# extboard.net
KiCad netlist of a schematic drawn in EAGLE
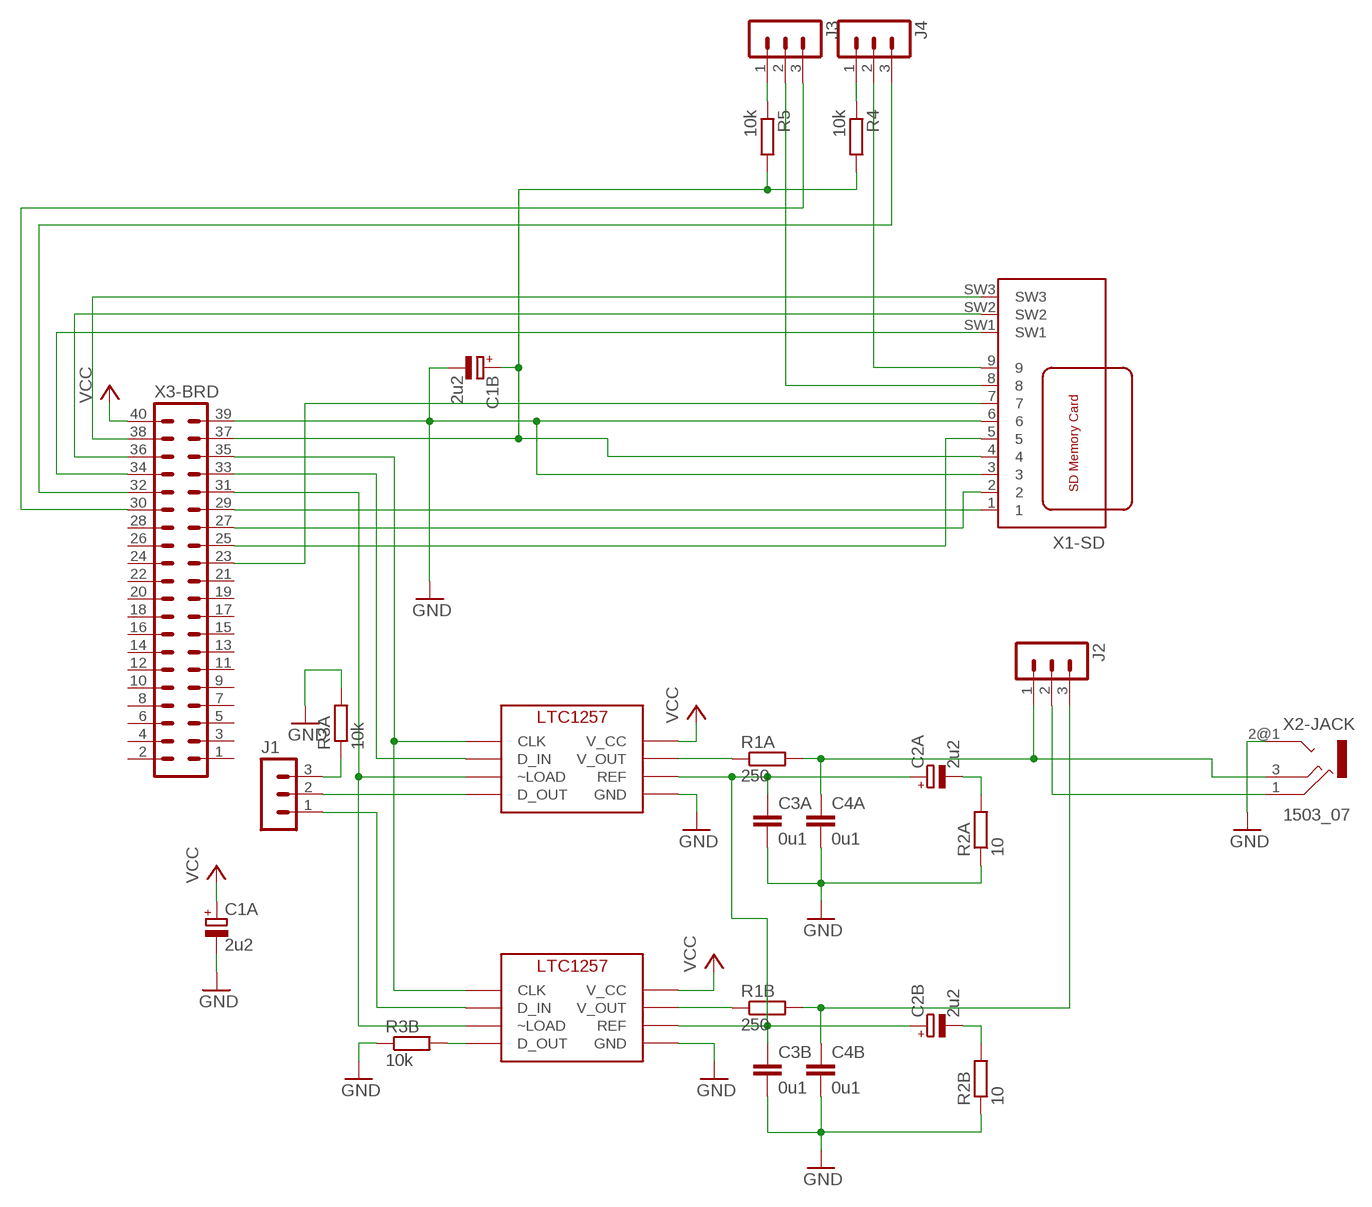
[diagram p0: schematic, sheet 1]

(export (version "E")
  (design (tool "Eeschema 10.0.6"))
  (components
    (comp (ref "C1A")
      (value "2u2")
      (footprint "eagle-import:E2,5-7")
      (libsource (lib "eagle-import") (part "CPOL-EUE2.5-7"))
    )
    (comp (ref "C1B")
      (value "2u2")
      (footprint "eagle-import:E2,5-7")
      (libsource (lib "eagle-import") (part "CPOL-EUE2.5-7"))
    )
    (comp (ref "C2A")
      (value "2u2")
      (footprint "eagle-import:E2,5-7")
      (libsource (lib "eagle-import") (part "CPOL-EUE2.5-7"))
    )
    (comp (ref "C2B")
      (value "2u2")
      (footprint "eagle-import:E2,5-7")
      (libsource (lib "eagle-import") (part "CPOL-EUE2.5-7"))
    )
    (comp (ref "C3A")
      (value "0u1")
      (footprint "eagle-import:C050-025X075")
      (libsource (lib "eagle-import") (part "C-EU050-025X075"))
    )
    (comp (ref "C3B")
      (value "0u1")
      (footprint "eagle-import:C050-025X075")
      (libsource (lib "eagle-import") (part "C-EU050-025X075"))
    )
    (comp (ref "C4A")
      (value "0u1")
      (footprint "eagle-import:C050-025X075")
      (libsource (lib "eagle-import") (part "C-EU050-025X075"))
    )
    (comp (ref "C4B")
      (value "0u1")
      (footprint "eagle-import:C050-025X075")
      (libsource (lib "eagle-import") (part "C-EU050-025X075"))
    )
    (comp (ref "J1")
      (value "MA03-1")
      (footprint "eagle-import:MA03-1")
      (libsource (lib "eagle-import") (part "MA03-1"))
    )
    (comp (ref "J2")
      (value "MA03-1")
      (footprint "eagle-import:MA03-1")
      (libsource (lib "eagle-import") (part "MA03-1"))
    )
    (comp (ref "J3")
      (value "MA03-1")
      (footprint "eagle-import:MA03-1")
      (fields (field (name "OC_FARNELL") "unknown") (field (name "OC_NEWARK") "unknown"))
      (libsource (lib "eagle-import") (part "MA03-1"))
    )
    (comp (ref "J4")
      (value "MA03-1")
      (footprint "eagle-import:MA03-1")
      (fields (field (name "OC_FARNELL") "unknown") (field (name "OC_NEWARK") "unknown"))
      (libsource (lib "eagle-import") (part "MA03-1"))
    )
    (comp (ref "R1A")
      (value "250")
      (footprint "eagle-import:0207_10")
      (libsource (lib "eagle-import") (part "R-EU_0207/10"))
    )
    (comp (ref "R1B")
      (value "250")
      (footprint "eagle-import:0207_10")
      (libsource (lib "eagle-import") (part "R-EU_0207/10"))
    )
    (comp (ref "R2A")
      (value "10")
      (footprint "eagle-import:0207_10")
      (libsource (lib "eagle-import") (part "R-EU_0207/10"))
    )
    (comp (ref "R2B")
      (value "10")
      (footprint "eagle-import:0207_10")
      (libsource (lib "eagle-import") (part "R-EU_0207/10"))
    )
    (comp (ref "R3A")
      (value "10k")
      (footprint "eagle-import:0207_10")
      (libsource (lib "eagle-import") (part "R-EU_0207/10"))
    )
    (comp (ref "R3B")
      (value "10k")
      (footprint "eagle-import:0207_10")
      (libsource (lib "eagle-import") (part "R-EU_0207/10"))
    )
    (comp (ref "R4")
      (value "10k")
      (footprint "eagle-import:0207_10")
      (libsource (lib "eagle-import") (part "R-EU_0207/10"))
    )
    (comp (ref "R5")
      (value "10k")
      (footprint "eagle-import:0207_10")
      (libsource (lib "eagle-import") (part "R-EU_0207/10"))
    )
    (comp (ref "U1")
      (value "LTC1257")
      (footprint "eagle-import:DIL-8")
      (libsource (lib "eagle-import") (part "LTC1257"))
    )
    (comp (ref "U2")
      (value "LTC1257")
      (footprint "eagle-import:DIL-8")
      (libsource (lib "eagle-import") (part "LTC1257"))
    )
    (comp (ref "X1-SD")
      (value "SDBMF")
      (footprint "eagle-import:SDBMF-009XXBXX2")
      (libsource (lib "eagle-import") (part "SDBMF"))
    )
    (comp (ref "X2-JACK")
      (value "1503_07")
      (footprint "eagle-import:1503_07")
      (fields (field (name "OC_FARNELL") "unknown"))
      (libsource (lib "eagle-import") (part "1503_?07"))
    )
    (comp (ref "X3-BRD")
      (value "MA20-2W")
      (footprint "eagle-import:MA20-2W")
      (libsource (lib "eagle-import") (part "MA20-2W"))
    )
  )
  (nets
    (net (code "1") (name "GND") (class "Default")
      (node (ref "C1A") (pin "-") (pinfunction "-_-") (pintype "passive"))
      (node (ref "C1B") (pin "-") (pinfunction "-_-") (pintype "passive"))
      (node (ref "C3A") (pin "2") (pinfunction "2_2") (pintype "passive"))
      (node (ref "C3B") (pin "2") (pinfunction "2_2") (pintype "passive"))
      (node (ref "C4A") (pin "2") (pinfunction "2_2") (pintype "passive"))
      (node (ref "C4B") (pin "2") (pinfunction "2_2") (pintype "passive"))
      (node (ref "R2A") (pin "1") (pinfunction "1_1") (pintype "passive"))
      (node (ref "R2B") (pin "1") (pinfunction "1_1") (pintype "passive"))
      (node (ref "R3A") (pin "2") (pinfunction "2_2") (pintype "passive"))
      (node (ref "R3B") (pin "1") (pinfunction "1_1") (pintype "passive"))
      (node (ref "U1") (pin "P$5") (pinfunction "GND_P$5") (pintype "power_in"))
      (node (ref "U2") (pin "P$5") (pinfunction "GND_P$5") (pintype "power_in"))
      (node (ref "X1-SD") (pin "3") (pinfunction "3_3") (pintype "passive"))
      (node (ref "X1-SD") (pin "6") (pinfunction "6_6") (pintype "passive"))
      (node (ref "X2-JACK") (pin "2@1") (pinfunction "2_2@1") (pintype "passive"))
      (node (ref "X3-BRD") (pin "39") (pinfunction "39_39") (pintype "passive"))
    )
    (net (code "2") (name "Net-(C1B-Pad+)") (class "Default")
      (node (ref "C1B") (pin "+") (pinfunction "+_+") (pintype "passive"))
      (node (ref "R4") (pin "2") (pinfunction "2_2") (pintype "passive"))
      (node (ref "R5") (pin "2") (pinfunction "2_2") (pintype "passive"))
      (node (ref "X1-SD") (pin "4") (pinfunction "4_4") (pintype "passive"))
      (node (ref "X3-BRD") (pin "37") (pinfunction "37_37") (pintype "passive"))
    )
    (net (code "3") (name "Net-(C2A-Pad-)") (class "Default")
      (node (ref "C2A") (pin "-") (pinfunction "-_-") (pintype "passive"))
      (node (ref "R2A") (pin "2") (pinfunction "2_2") (pintype "passive"))
    )
    (net (code "4") (name "Net-(C2B-Pad-)") (class "Default")
      (node (ref "C2B") (pin "-") (pinfunction "-_-") (pintype "passive"))
      (node (ref "R2B") (pin "2") (pinfunction "2_2") (pintype "passive"))
    )
    (net (code "5") (name "Net-(C4A-Pad1)") (class "Default")
      (node (ref "C4A") (pin "1") (pinfunction "1_1") (pintype "passive"))
      (node (ref "J2") (pin "1") (pinfunction "1_1") (pintype "passive"))
      (node (ref "R1A") (pin "2") (pinfunction "2_2") (pintype "passive"))
      (node (ref "X2-JACK") (pin "3") (pinfunction "3_3") (pintype "passive"))
    )
    (net (code "6") (name "Net-(C4B-Pad1)") (class "Default")
      (node (ref "C4B") (pin "1") (pinfunction "1_1") (pintype "passive"))
      (node (ref "J2") (pin "3") (pinfunction "3_3") (pintype "passive"))
      (node (ref "R1B") (pin "2") (pinfunction "2_2") (pintype "passive"))
    )
    (net (code "7") (name "Net-(J1-Pad3)") (class "Default")
      (node (ref "J1") (pin "3") (pinfunction "3_3") (pintype "passive"))
      (node (ref "R3A") (pin "1") (pinfunction "1_1") (pintype "passive"))
    )
    (net (code "8") (name "Net-(J2-Pad2)") (class "Default")
      (node (ref "J2") (pin "2") (pinfunction "2_2") (pintype "passive"))
      (node (ref "X2-JACK") (pin "1") (pinfunction "1_1") (pintype "passive"))
    )
    (net (code "9") (name "Net-(J3-Pad1)") (class "Default")
      (node (ref "J3") (pin "1") (pinfunction "1_1") (pintype "passive"))
      (node (ref "R5") (pin "1") (pinfunction "1_1") (pintype "passive"))
    )
    (net (code "10") (name "Net-(J3-Pad2)") (class "Default")
      (node (ref "J3") (pin "2") (pinfunction "2_2") (pintype "passive"))
      (node (ref "X1-SD") (pin "8") (pinfunction "8_8") (pintype "passive"))
    )
    (net (code "11") (name "Net-(J3-Pad3)") (class "Default")
      (node (ref "J3") (pin "3") (pinfunction "3_3") (pintype "passive"))
      (node (ref "X3-BRD") (pin "30") (pinfunction "30_30") (pintype "passive"))
    )
    (net (code "12") (name "Net-(J4-Pad1)") (class "Default")
      (node (ref "J4") (pin "1") (pinfunction "1_1") (pintype "passive"))
      (node (ref "R4") (pin "1") (pinfunction "1_1") (pintype "passive"))
    )
    (net (code "13") (name "Net-(J4-Pad2)") (class "Default")
      (node (ref "J4") (pin "2") (pinfunction "2_2") (pintype "passive"))
      (node (ref "X1-SD") (pin "9") (pinfunction "9_9") (pintype "passive"))
    )
    (net (code "14") (name "Net-(J4-Pad3)") (class "Default")
      (node (ref "J4") (pin "3") (pinfunction "3_3") (pintype "passive"))
      (node (ref "X3-BRD") (pin "32") (pinfunction "32_32") (pintype "passive"))
    )
    (net (code "15") (name "Net-(U1-CLK)") (class "Default")
      (node (ref "U1") (pin "P$1") (pinfunction "CLK_P$1") (pintype "input"))
      (node (ref "U2") (pin "P$1") (pinfunction "CLK_P$1") (pintype "input"))
      (node (ref "X3-BRD") (pin "35") (pinfunction "35_35") (pintype "passive"))
    )
    (net (code "16") (name "Net-(U1-D_IN)") (class "Default")
      (node (ref "U1") (pin "P$2") (pinfunction "D_IN_P$2") (pintype "input"))
      (node (ref "X3-BRD") (pin "33") (pinfunction "33_33") (pintype "passive"))
    )
    (net (code "17") (name "Net-(U1-D_OUT)") (class "Default")
      (node (ref "J1") (pin "2") (pinfunction "2_2") (pintype "passive"))
      (node (ref "U1") (pin "P$4") (pinfunction "D_OUT_P$4") (pintype "output"))
    )
    (net (code "18") (name "Net-(U1-REF)") (class "Default")
      (node (ref "C2A") (pin "+") (pinfunction "+_+") (pintype "passive"))
      (node (ref "C2B") (pin "+") (pinfunction "+_+") (pintype "passive"))
      (node (ref "C3A") (pin "1") (pinfunction "1_1") (pintype "passive"))
      (node (ref "C3B") (pin "1") (pinfunction "1_1") (pintype "passive"))
      (node (ref "U1") (pin "P$6") (pinfunction "REF_P$6") (pintype "power_in"))
      (node (ref "U2") (pin "P$6") (pinfunction "REF_P$6") (pintype "power_in"))
    )
    (net (code "19") (name "Net-(U1-V_OUT)") (class "Default")
      (node (ref "R1A") (pin "1") (pinfunction "1_1") (pintype "passive"))
      (node (ref "U1") (pin "P$7") (pinfunction "V_OUT_P$7") (pintype "output"))
    )
    (net (code "20") (name "Net-(U1-~{LOAD})") (class "Default")
      (node (ref "U1") (pin "P$3") (pinfunction "~{LOAD}_P$3") (pintype "input"))
      (node (ref "U2") (pin "P$3") (pinfunction "~{LOAD}_P$3") (pintype "input"))
      (node (ref "X3-BRD") (pin "31") (pinfunction "31_31") (pintype "passive"))
    )
    (net (code "21") (name "Net-(U2-D_IN)") (class "Default")
      (node (ref "J1") (pin "1") (pinfunction "1_1") (pintype "passive"))
      (node (ref "U2") (pin "P$2") (pinfunction "D_IN_P$2") (pintype "input"))
    )
    (net (code "22") (name "Net-(U2-D_OUT)") (class "Default")
      (node (ref "R3B") (pin "2") (pinfunction "2_2") (pintype "passive"))
      (node (ref "U2") (pin "P$4") (pinfunction "D_OUT_P$4") (pintype "output"))
    )
    (net (code "23") (name "Net-(U2-V_OUT)") (class "Default")
      (node (ref "R1B") (pin "1") (pinfunction "1_1") (pintype "passive"))
      (node (ref "U2") (pin "P$7") (pinfunction "V_OUT_P$7") (pintype "output"))
    )
    (net (code "24") (name "Net-(X1-SD-Pad1)") (class "Default")
      (node (ref "X1-SD") (pin "1") (pinfunction "1_1") (pintype "passive"))
      (node (ref "X3-BRD") (pin "29") (pinfunction "29_29") (pintype "passive"))
    )
    (net (code "25") (name "Net-(X1-SD-Pad2)") (class "Default")
      (node (ref "X1-SD") (pin "2") (pinfunction "2_2") (pintype "passive"))
      (node (ref "X3-BRD") (pin "27") (pinfunction "27_27") (pintype "passive"))
    )
    (net (code "26") (name "Net-(X1-SD-Pad5)") (class "Default")
      (node (ref "X1-SD") (pin "5") (pinfunction "5_5") (pintype "passive"))
      (node (ref "X3-BRD") (pin "25") (pinfunction "25_25") (pintype "passive"))
    )
    (net (code "27") (name "Net-(X1-SD-Pad7)") (class "Default")
      (node (ref "X1-SD") (pin "7") (pinfunction "7_7") (pintype "passive"))
      (node (ref "X3-BRD") (pin "23") (pinfunction "23_23") (pintype "passive"))
    )
    (net (code "28") (name "Net-(X1-SD-PadSW1)") (class "Default")
      (node (ref "X1-SD") (pin "SW1") (pinfunction "SW1_SW1") (pintype "passive"))
      (node (ref "X3-BRD") (pin "34") (pinfunction "34_34") (pintype "passive"))
    )
    (net (code "29") (name "Net-(X1-SD-PadSW2)") (class "Default")
      (node (ref "X1-SD") (pin "SW2") (pinfunction "SW2_SW2") (pintype "passive"))
      (node (ref "X3-BRD") (pin "36") (pinfunction "36_36") (pintype "passive"))
    )
    (net (code "30") (name "Net-(X1-SD-PadSW3)") (class "Default")
      (node (ref "X1-SD") (pin "SW3") (pinfunction "SW3_SW3") (pintype "passive"))
      (node (ref "X3-BRD") (pin "38") (pinfunction "38_38") (pintype "passive"))
    )
    (net (code "31") (name "VCC") (class "Default")
      (node (ref "C1A") (pin "+") (pinfunction "+_+") (pintype "passive"))
      (node (ref "U1") (pin "P$8") (pinfunction "V_CC_P$8") (pintype "power_in"))
      (node (ref "U2") (pin "P$8") (pinfunction "V_CC_P$8") (pintype "power_in"))
      (node (ref "X3-BRD") (pin "40") (pinfunction "40_40") (pintype "passive"))
    )
    (net (code "32") (name "unconnected-(X2-JACK-2-Pad2@2)") (class "Default")
      (node (ref "X2-JACK") (pin "2@2") (pinfunction "2_2@2") (pintype "passive"))
    )
    (net (code "33") (name "unconnected-(X3-BRD-Pad1)") (class "Default")
      (node (ref "X3-BRD") (pin "1") (pinfunction "1_1") (pintype "passive"))
    )
    (net (code "34") (name "unconnected-(X3-BRD-Pad2)") (class "Default")
      (node (ref "X3-BRD") (pin "2") (pinfunction "2_2") (pintype "passive"))
    )
    (net (code "35") (name "unconnected-(X3-BRD-Pad3)") (class "Default")
      (node (ref "X3-BRD") (pin "3") (pinfunction "3_3") (pintype "passive"))
    )
    (net (code "36") (name "unconnected-(X3-BRD-Pad4)") (class "Default")
      (node (ref "X3-BRD") (pin "4") (pinfunction "4_4") (pintype "passive"))
    )
    (net (code "37") (name "unconnected-(X3-BRD-Pad5)") (class "Default")
      (node (ref "X3-BRD") (pin "5") (pinfunction "5_5") (pintype "passive"))
    )
    (net (code "38") (name "unconnected-(X3-BRD-Pad6)") (class "Default")
      (node (ref "X3-BRD") (pin "6") (pinfunction "6_6") (pintype "passive"))
    )
    (net (code "39") (name "unconnected-(X3-BRD-Pad7)") (class "Default")
      (node (ref "X3-BRD") (pin "7") (pinfunction "7_7") (pintype "passive"))
    )
    (net (code "40") (name "unconnected-(X3-BRD-Pad8)") (class "Default")
      (node (ref "X3-BRD") (pin "8") (pinfunction "8_8") (pintype "passive"))
    )
    (net (code "41") (name "unconnected-(X3-BRD-Pad9)") (class "Default")
      (node (ref "X3-BRD") (pin "9") (pinfunction "9_9") (pintype "passive"))
    )
    (net (code "42") (name "unconnected-(X3-BRD-Pad10)") (class "Default")
      (node (ref "X3-BRD") (pin "10") (pinfunction "10_10") (pintype "passive"))
    )
    (net (code "43") (name "unconnected-(X3-BRD-Pad11)") (class "Default")
      (node (ref "X3-BRD") (pin "11") (pinfunction "11_11") (pintype "passive"))
    )
    (net (code "44") (name "unconnected-(X3-BRD-Pad12)") (class "Default")
      (node (ref "X3-BRD") (pin "12") (pinfunction "12_12") (pintype "passive"))
    )
    (net (code "45") (name "unconnected-(X3-BRD-Pad13)") (class "Default")
      (node (ref "X3-BRD") (pin "13") (pinfunction "13_13") (pintype "passive"))
    )
    (net (code "46") (name "unconnected-(X3-BRD-Pad14)") (class "Default")
      (node (ref "X3-BRD") (pin "14") (pinfunction "14_14") (pintype "passive"))
    )
    (net (code "47") (name "unconnected-(X3-BRD-Pad15)") (class "Default")
      (node (ref "X3-BRD") (pin "15") (pinfunction "15_15") (pintype "passive"))
    )
    (net (code "48") (name "unconnected-(X3-BRD-Pad16)") (class "Default")
      (node (ref "X3-BRD") (pin "16") (pinfunction "16_16") (pintype "passive"))
    )
    (net (code "49") (name "unconnected-(X3-BRD-Pad17)") (class "Default")
      (node (ref "X3-BRD") (pin "17") (pinfunction "17_17") (pintype "passive"))
    )
    (net (code "50") (name "unconnected-(X3-BRD-Pad18)") (class "Default")
      (node (ref "X3-BRD") (pin "18") (pinfunction "18_18") (pintype "passive"))
    )
    (net (code "51") (name "unconnected-(X3-BRD-Pad19)") (class "Default")
      (node (ref "X3-BRD") (pin "19") (pinfunction "19_19") (pintype "passive"))
    )
    (net (code "52") (name "unconnected-(X3-BRD-Pad20)") (class "Default")
      (node (ref "X3-BRD") (pin "20") (pinfunction "20_20") (pintype "passive"))
    )
    (net (code "53") (name "unconnected-(X3-BRD-Pad21)") (class "Default")
      (node (ref "X3-BRD") (pin "21") (pinfunction "21_21") (pintype "passive"))
    )
    (net (code "54") (name "unconnected-(X3-BRD-Pad22)") (class "Default")
      (node (ref "X3-BRD") (pin "22") (pinfunction "22_22") (pintype "passive"))
    )
    (net (code "55") (name "unconnected-(X3-BRD-Pad24)") (class "Default")
      (node (ref "X3-BRD") (pin "24") (pinfunction "24_24") (pintype "passive"))
    )
    (net (code "56") (name "unconnected-(X3-BRD-Pad26)") (class "Default")
      (node (ref "X3-BRD") (pin "26") (pinfunction "26_26") (pintype "passive"))
    )
    (net (code "57") (name "unconnected-(X3-BRD-Pad28)") (class "Default")
      (node (ref "X3-BRD") (pin "28") (pinfunction "28_28") (pintype "passive"))
    )
  )
)
